# ADC_Module.net
KiCad netlist of a schematic drawn in Altium Designer
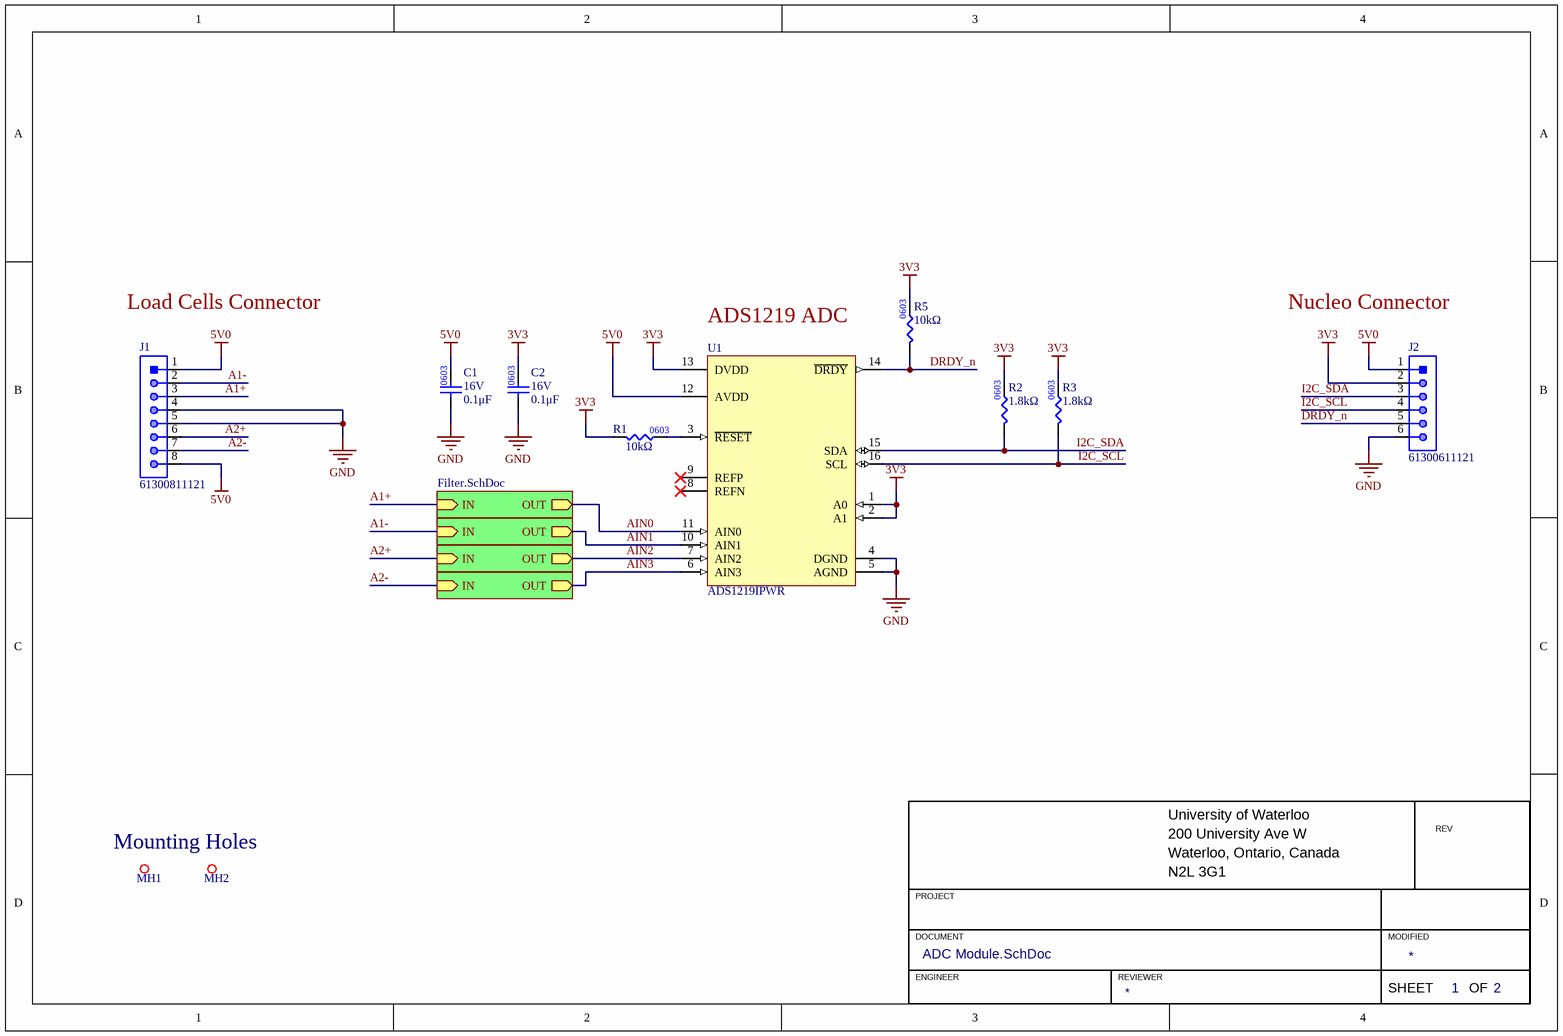
[diagram p0: ADC Module.SchDoc]

(export (version "E")
  (design (tool "Eeschema 10.0.6"))
  (components
    (comp (ref "C1")
      (value "0.1μF")
      (footprint "CAP0603")
      (description "CAP CER 0.1UF 16V X7R 0603")
      (fields (field (name "VOLTAGE RATING") "16V") (field (name "Comment") "CAP_0.1uF_16V_0603"))
      (libsource (lib "Personal_Schematic_Library_2022") (part "CAP_0.1uF_16V_0603"))
    )
    (comp (ref "C2")
      (value "0.1μF")
      (footprint "CAP0603")
      (description "CAP CER 0.1UF 16V X7R 0603")
      (fields (field (name "VOLTAGE RATING") "16V") (field (name "Comment") "CAP_0.1uF_16V_0603"))
      (libsource (lib "Personal_Schematic_Library_2022") (part "CAP_0.1uF_16V_0603"))
    )
    (comp (ref "J1")
      (value "HEADER 8x1")
      (footprint "HDR1X8")
      (description "CONN HEADER VERT 8POS 2.54MM")
      (fields (field (name "MANUFACTURER PART NUMBER 1") "61300811121"))
      (libsource (lib "Personal_Schematic_Library_2022") (part "HEADER 8x1"))
    )
    (comp (ref "J2")
      (value "HEADER 6x1")
      (footprint "HDR1X6")
      (description "CONN HEADER VERT 6POS 2.54MM")
      (fields (field (name "MANUFACTURER PART NUMBER 1") "61300611121"))
      (libsource (lib "Personal_Schematic_Library_2022") (part "HEADER 6x1"))
    )
    (comp (ref "MH1")
      (value "MOUNTING_HOLE_M3")
      (footprint "MOUNTING_HOLE_3mm")
      (libsource (lib "UWRT_Schematic_Library_2020") (part "MOUNTING_HOLE_M3"))
    )
    (comp (ref "MH2")
      (value "MOUNTING_HOLE_M3")
      (footprint "MOUNTING_HOLE_3mm")
      (libsource (lib "UWRT_Schematic_Library_2020") (part "MOUNTING_HOLE_M3"))
    )
    (comp (ref "R1")
      (value "10kΩ")
      (footprint "RES0603")
      (description "RES 10K OHM 1% 1/8W 0603")
      (fields (field (name "Comment") "RES_10kΩ_0603_1%"))
      (libsource (lib "Personal_Schematic_Library_2022") (part "RES_10kΩ_0603_1%"))
    )
    (comp (ref "R2")
      (value "1.8kΩ")
      (footprint "RES0603")
      (description "RES 1.8K OHM 1% 1/10W 0603")
      (fields (field (name "Comment") "RES_1.8kΩ_0603_1%"))
      (libsource (lib "Personal_Schematic_Library_2022") (part "RES_1.8kΩ_0603_1%"))
    )
    (comp (ref "R3")
      (value "1.8kΩ")
      (footprint "RES0603")
      (description "RES 1.8K OHM 1% 1/10W 0603")
      (fields (field (name "Comment") "RES_1.8kΩ_0603_1%"))
      (libsource (lib "Personal_Schematic_Library_2022") (part "RES_1.8kΩ_0603_1%"))
    )
    (comp (ref "R5")
      (value "10kΩ")
      (footprint "RES0603")
      (description "RES 10K OHM 1% 1/8W 0603")
      (fields (field (name "Comment") "RES_10kΩ_0603_1%"))
      (libsource (lib "Personal_Schematic_Library_2022") (part "RES_10kΩ_0603_1%"))
    )
    (comp (ref "U1")
      (value "ADS1219IPWR")
      (footprint "TI_16-TSSOP")
      (description "IC ADC 24BIT SIGMA-DELTA 16TSSOP")
      (libsource (lib "Personal_Schematic_Library_2022") (part "ADS1219IPWR"))
    )
  )
  (nets
    (net (code "1") (name "/A1+") (class "Default")
      (node (ref "J1") (pin "3") (pinfunction "3_3") (pintype "passive"))
    )
    (net (code "2") (name "/A1-") (class "Default")
      (node (ref "J1") (pin "2") (pinfunction "2_2") (pintype "passive"))
    )
    (net (code "3") (name "/A2+") (class "Default")
      (node (ref "J1") (pin "6") (pinfunction "6_6") (pintype "passive"))
    )
    (net (code "4") (name "/A2-") (class "Default")
      (node (ref "J1") (pin "7") (pinfunction "7_7") (pintype "passive"))
    )
    (net (code "5") (name "/AIN0") (class "Default")
      (node (ref "U1") (pin "11") (pinfunction "AIN0_11") (pintype "input"))
    )
    (net (code "6") (name "/AIN1") (class "Default")
      (node (ref "U1") (pin "10") (pinfunction "AIN1_10") (pintype "input"))
    )
    (net (code "7") (name "/AIN2") (class "Default")
      (node (ref "U1") (pin "7") (pinfunction "AIN2_7") (pintype "input"))
    )
    (net (code "8") (name "/AIN3") (class "Default")
      (node (ref "U1") (pin "6") (pinfunction "AIN3_6") (pintype "input"))
    )
    (net (code "9") (name "/DRDY_n") (class "Default")
      (node (ref "J2") (pin "5") (pinfunction "5_5") (pintype "passive"))
      (node (ref "R5") (pin "1") (pinfunction "1_1") (pintype "passive"))
      (node (ref "U1") (pin "14") (pinfunction "~{DRDY}_14") (pintype "output"))
    )
    (net (code "10") (name "/I2C_SCL") (class "Default")
      (node (ref "J2") (pin "4") (pinfunction "4_4") (pintype "passive"))
      (node (ref "R3") (pin "1") (pinfunction "1_1") (pintype "passive"))
      (node (ref "U1") (pin "16") (pinfunction "SCL_16") (pintype "bidirectional"))
    )
    (net (code "11") (name "/I2C_SDA") (class "Default")
      (node (ref "J2") (pin "3") (pinfunction "3_3") (pintype "passive"))
      (node (ref "R2") (pin "1") (pinfunction "1_1") (pintype "passive"))
      (node (ref "U1") (pin "15") (pinfunction "SDA_15") (pintype "bidirectional"))
    )
    (net (code "12") (name "3V3") (class "Default")
      (node (ref "C2") (pin "2") (pinfunction "2_2") (pintype "passive"))
      (node (ref "J2") (pin "2") (pinfunction "2_2") (pintype "passive"))
      (node (ref "R1") (pin "1") (pinfunction "1_1") (pintype "passive"))
      (node (ref "R2") (pin "2") (pinfunction "2_2") (pintype "passive"))
      (node (ref "R3") (pin "2") (pinfunction "2_2") (pintype "passive"))
      (node (ref "R5") (pin "2") (pinfunction "2_2") (pintype "passive"))
      (node (ref "U1") (pin "1") (pinfunction "A0_1") (pintype "input"))
      (node (ref "U1") (pin "13") (pinfunction "DVDD_13") (pintype "power_in"))
      (node (ref "U1") (pin "2") (pinfunction "A1_2") (pintype "input"))
    )
    (net (code "13") (name "5V0") (class "Default")
      (node (ref "C1") (pin "2") (pinfunction "2_2") (pintype "passive"))
      (node (ref "J1") (pin "1") (pinfunction "1_1") (pintype "passive"))
      (node (ref "J1") (pin "8") (pinfunction "8_8") (pintype "passive"))
      (node (ref "J2") (pin "1") (pinfunction "1_1") (pintype "passive"))
      (node (ref "U1") (pin "12") (pinfunction "AVDD_12") (pintype "power_in"))
    )
    (net (code "14") (name "GND") (class "Default")
      (node (ref "C1") (pin "1") (pinfunction "1_1") (pintype "passive"))
      (node (ref "C2") (pin "1") (pinfunction "1_1") (pintype "passive"))
      (node (ref "J1") (pin "4") (pinfunction "4_4") (pintype "passive"))
      (node (ref "J1") (pin "5") (pinfunction "5_5") (pintype "passive"))
      (node (ref "J2") (pin "6") (pinfunction "6_6") (pintype "passive"))
      (node (ref "U1") (pin "4") (pinfunction "DGND_4") (pintype "power_in"))
      (node (ref "U1") (pin "5") (pinfunction "AGND_5") (pintype "power_in"))
    )
    (net (code "15") (name "Net-(U1-~{RESET})") (class "Default")
      (node (ref "R1") (pin "2") (pinfunction "2_2") (pintype "passive"))
      (node (ref "U1") (pin "3") (pinfunction "~{RESET}_3") (pintype "input"))
    )
    (net (code "16") (name "unconnected-(U1-REFN-Pad8)") (class "Default")
      (node (ref "U1") (pin "8") (pinfunction "REFN_8") (pintype "power_in+no_connect"))
    )
    (net (code "17") (name "unconnected-(U1-REFP-Pad9)") (class "Default")
      (node (ref "U1") (pin "9") (pinfunction "REFP_9") (pintype "power_in+no_connect"))
    )
  )
)
